# new_work_1.net
KiCad netlist of a schematic drawn in EAGLE
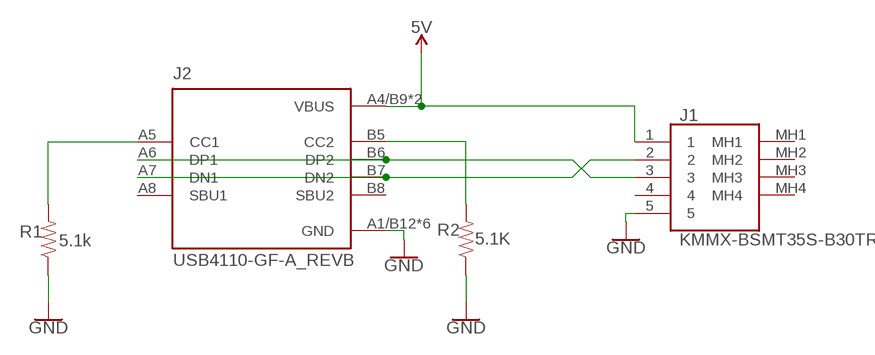
[diagram p0: schematic, sheet 1]

(export (version "E")
  (design (tool "Eeschema 10.0.6"))
  (components
    (comp (ref "J1")
      (value "KMMX-BSMT35S-B30TR")
      (footprint "eagle-import:KMMXBSMT35SB30TR")
      (fields (field (name "MOUSER_PART_NUMBER") "806-KMMXBSMT35SB30TR"))
      (libsource (lib "eagle-import") (part "KMMX-BSMT35S-B30TR"))
    )
    (comp (ref "J2")
      (value "USB4110-GF-A_REVB")
      (footprint "eagle-import:GCT_USB4110-GF-A_REVB")
      (fields (field (name "MF") "GCT") (field (name "MP") "USB4110-GF-A"))
      (libsource (lib "eagle-import") (part "USB4110-GF-A_REVB"))
    )
    (comp (ref "R1")
      (value "5.1k")
      (footprint "eagle-import:0402-TIGHT")
      (libsource (lib "eagle-import") (part "RESISTOR0402T"))
    )
    (comp (ref "R2")
      (value "5.1K")
      (footprint "eagle-import:0402-TIGHT")
      (libsource (lib "eagle-import") (part "RESISTOR0402T"))
    )
  )
  (nets
    (net (code "1") (name "5V") (class "Default")
      (node (ref "J1") (pin "1") (pinfunction "1_1") (pintype "bidirectional"))
      (node (ref "J2") (pin "A4/B9") (pinfunction "VBUS_A4/B9") (pintype "power_in"))
      (node (ref "J2") (pin "B4/A9") (pinfunction "VBUS_B4/A9") (pintype "power_in"))
    )
    (net (code "2") (name "GND") (class "Default")
      (node (ref "J1") (pin "5") (pinfunction "5_5") (pintype "bidirectional"))
      (node (ref "J2") (pin "A1/B12") (pinfunction "GND_A1/B12") (pintype "power_in"))
      (node (ref "J2") (pin "B1/A12") (pinfunction "GND_B1/A12") (pintype "power_in"))
      (node (ref "J2") (pin "S1") (pinfunction "GND_S1") (pintype "power_in"))
      (node (ref "J2") (pin "S2") (pinfunction "GND_S2") (pintype "power_in"))
      (node (ref "J2") (pin "S3") (pinfunction "GND_S3") (pintype "power_in"))
      (node (ref "J2") (pin "S4") (pinfunction "GND_S4") (pintype "power_in"))
      (node (ref "R1") (pin "1") (pinfunction "1_1") (pintype "passive"))
      (node (ref "R2") (pin "1") (pinfunction "1_1") (pintype "passive"))
    )
    (net (code "3") (name "Net-(J2-CC1)") (class "Default")
      (node (ref "J2") (pin "A5") (pinfunction "CC1_A5") (pintype "bidirectional"))
      (node (ref "R1") (pin "2") (pinfunction "2_2") (pintype "passive"))
    )
    (net (code "4") (name "Net-(J2-CC2)") (class "Default")
      (node (ref "J2") (pin "B5") (pinfunction "CC2_B5") (pintype "bidirectional"))
      (node (ref "R2") (pin "2") (pinfunction "2_2") (pintype "passive"))
    )
    (net (code "5") (name "Net-(J2-DN1)") (class "Default")
      (node (ref "J1") (pin "2") (pinfunction "2_2") (pintype "bidirectional"))
      (node (ref "J2") (pin "A7") (pinfunction "DN1_A7") (pintype "bidirectional"))
      (node (ref "J2") (pin "B7") (pinfunction "DN2_B7") (pintype "bidirectional"))
    )
    (net (code "6") (name "Net-(J2-DP1)") (class "Default")
      (node (ref "J1") (pin "3") (pinfunction "3_3") (pintype "bidirectional"))
      (node (ref "J2") (pin "A6") (pinfunction "DP1_A6") (pintype "bidirectional"))
      (node (ref "J2") (pin "B6") (pinfunction "DP2_B6") (pintype "bidirectional"))
    )
    (net (code "7") (name "unconnected-(J1-Pad4)") (class "Default")
      (node (ref "J1") (pin "4") (pinfunction "4_4") (pintype "bidirectional"))
    )
    (net (code "8") (name "unconnected-(J1-PadMH1)") (class "Default")
      (node (ref "J1") (pin "MH1") (pinfunction "MH1_MH1") (pintype "bidirectional"))
    )
    (net (code "9") (name "unconnected-(J1-PadMH2)") (class "Default")
      (node (ref "J1") (pin "MH2") (pinfunction "MH2_MH2") (pintype "bidirectional"))
    )
    (net (code "10") (name "unconnected-(J1-PadMH3)") (class "Default")
      (node (ref "J1") (pin "MH3") (pinfunction "MH3_MH3") (pintype "bidirectional"))
    )
    (net (code "11") (name "unconnected-(J1-PadMH4)") (class "Default")
      (node (ref "J1") (pin "MH4") (pinfunction "MH4_MH4") (pintype "bidirectional"))
    )
    (net (code "12") (name "unconnected-(J2-SBU1-PadA8)") (class "Default")
      (node (ref "J2") (pin "A8") (pinfunction "SBU1_A8") (pintype "bidirectional"))
    )
    (net (code "13") (name "unconnected-(J2-SBU2-PadB8)") (class "Default")
      (node (ref "J2") (pin "B8") (pinfunction "SBU2_B8") (pintype "bidirectional"))
    )
  )
)
